# untitled.net
KiCad netlist of a schematic drawn in EAGLE
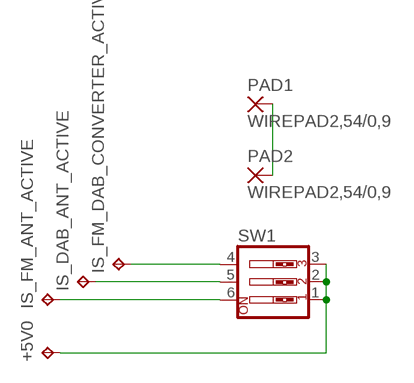
[diagram p0: schematic, sheet 1]

(export (version "E")
  (design (tool "Eeschema 10.0.6"))
  (components
    (comp (ref "+5V0")
      (value "TPPAD1-13")
      (footprint "eagle-import:P1-13")
      (libsource (lib "eagle-import") (part "TPPAD1-13"))
    )
    (comp (ref "IS_DAB_ANT_ACTIVE")
      (value "TPPAD1-13")
      (footprint "eagle-import:P1-13")
      (libsource (lib "eagle-import") (part "TPPAD1-13"))
    )
    (comp (ref "IS_FM_ANT_ACTIVE")
      (value "TPPAD1-13")
      (footprint "eagle-import:P1-13")
      (libsource (lib "eagle-import") (part "TPPAD1-13"))
    )
    (comp (ref "IS_FM_DAB_CONVERTER_ACTIVE")
      (value "TPPAD1-13")
      (footprint "eagle-import:P1-13")
      (libsource (lib "eagle-import") (part "TPPAD1-13"))
    )
    (comp (ref "PAD1")
      (value "WIREPAD2,54/0,9")
      (footprint "eagle-import:2,54_0,9")
      (libsource (lib "eagle-import") (part "WIREPAD2,54/0,9"))
    )
    (comp (ref "PAD2")
      (value "WIREPAD2,54/0,9")
      (footprint "eagle-import:2,54_0,9")
      (libsource (lib "eagle-import") (part "WIREPAD2,54/0,9"))
    )
    (comp (ref "SW1")
      (value "SW_DIP-3")
      (footprint "eagle-import:EDG-03")
      (libsource (lib "eagle-import") (part "SW_DIP-3"))
    )
  )
  (nets
    (net (code "1") (name "Net-(+5V0-PadTP)") (class "Default")
      (node (ref "+5V0") (pin "TP") (pinfunction "TP_TP") (pintype "input"))
      (node (ref "SW1") (pin "1") (pinfunction "1_1") (pintype "passive"))
      (node (ref "SW1") (pin "2") (pinfunction "2_2") (pintype "passive"))
      (node (ref "SW1") (pin "3") (pinfunction "3_3") (pintype "passive"))
    )
    (net (code "2") (name "Net-(IS_DAB_ANT_ACTIVE-PadTP)") (class "Default")
      (node (ref "IS_DAB_ANT_ACTIVE") (pin "TP") (pinfunction "TP_TP") (pintype "input"))
      (node (ref "SW1") (pin "5") (pinfunction "5_5") (pintype "passive"))
    )
    (net (code "3") (name "Net-(IS_FM_ANT_ACTIVE-PadTP)") (class "Default")
      (node (ref "IS_FM_ANT_ACTIVE") (pin "TP") (pinfunction "TP_TP") (pintype "input"))
      (node (ref "SW1") (pin "6") (pinfunction "6_6") (pintype "passive"))
    )
    (net (code "4") (name "Net-(IS_FM_DAB_CONVERTER_ACTIVE-PadTP)") (class "Default")
      (node (ref "IS_FM_DAB_CONVERTER_ACTIVE") (pin "TP") (pinfunction "TP_TP") (pintype "input"))
      (node (ref "SW1") (pin "4") (pinfunction "4_4") (pintype "passive"))
    )
    (net (code "5") (name "Net-(PAD1-P)") (class "Default")
      (node (ref "PAD1") (pin "1") (pinfunction "P_1") (pintype "passive"))
      (node (ref "PAD2") (pin "1") (pinfunction "P_1") (pintype "passive"))
    )
  )
)
